# Step_Down.net
KiCad netlist of a schematic drawn in Altium Designer
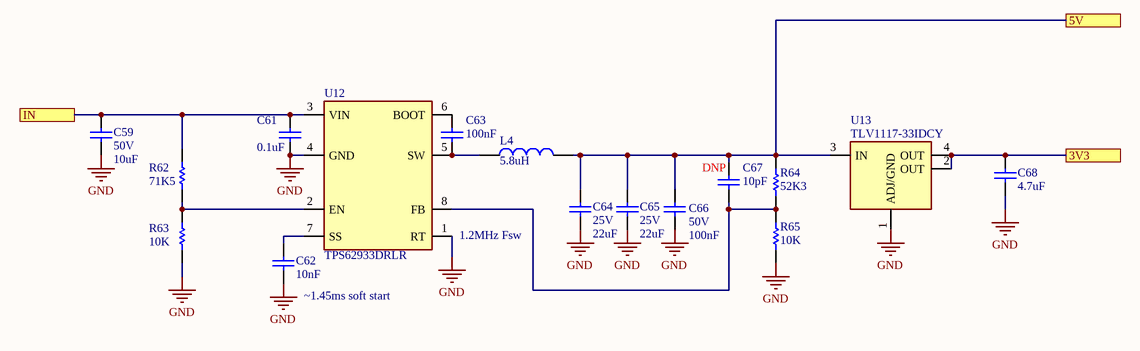
[diagram p0: Step_Down.SchDoc]

(export (version "E")
  (design (tool "Eeschema 10.0.6"))
  (components
    (comp (ref "C59")
      (value "CL32B106KBJNNNE")
      (footprint "CAPC1210X090")
      (description "10 µF ±10% 50V Ceramic Capacitor X7R 1210 (3225 Metric)")
      (fields
        (field (name "DISTRIBUTOR PART NUMBER") "1276-3387-1-ND")
        (field (name "TOLERANCE") "10%")
        (field (name "VOLTAGE RATING") "50V")
        (field (name "CAPACITANCE") "10uF")
      )
      (libsource (lib "Ahristi_Library") (part "CL32B106KBJNNNE"))
    )
    (comp (ref "C61")
      (value "CL05B104KB5NNNC")
      (footprint "CAPC0402X020")
      (description "0.1 µF ±10% 50V Ceramic Capacitor X7R 0402 (1005 Metric)")
      (fields
        (field (name "TOLERANCE") "10%")
        (field (name "DISTRIBUTOR PART NUMBER") "1276-CL05B104KB5NNNCCT-ND")
        (field (name "CAPACITANCE") "0.1uF")
      )
      (libsource (lib "Ahristi_Library") (part "CL05B104KB5NNNC"))
    )
    (comp (ref "C62")
      (value "CL10B103KB8NNNC")
      (footprint "CAPC0603X060")
      (description "10nF ±10% 50V Ceramic Capacitor X7R 0603 (1608 Metric)")
      (fields
        (field (name "DISTRIBUTOR PART NUMBER") "1276-1009-1-ND")
        (field (name "TOLERANCE") "10%")
        (field (name "CAPACITANCE") "10nF")
      )
      (libsource (lib "Ahristi_Library") (part "CL10B103KB8NNNC"))
    )
    (comp (ref "C63")
      (value "C0603C104K5RACTU")
      (footprint "CAPC0603X040")
      (description "0.1 µF ±10% 50V Ceramic Capacitor X7R 0603 (1608 Metric)")
      (fields
        (field (name "DISTRIBUTOR PART NUMBER") "399-C0603C104K5RACTUCT-ND")
        (field (name "TOLERANCE") "10%")
        (field (name "CAPACITANCE") "100nF")
      )
      (libsource (lib "Ahristi_Library") (part "C0603C104K5RACTU"))
    )
    (comp (ref "C64")
      (value "CL32B226KAJNNNE")
      (footprint "CAPC1210X090")
      (description "22 µF ±10% 25V Ceramic Capacitor X7R 1210 (3225 Metric)")
      (fields
        (field (name "DISTRIBUTOR PART NUMBER") "1276-3392-1-ND")
        (field (name "TOLERANCE") "10%")
        (field (name "VOLTAGE RATING") "25V")
        (field (name "CAPACITANCE") "22uF")
      )
      (libsource (lib "Ahristi_Library") (part "CL32B226KAJNNNE"))
    )
    (comp (ref "C65")
      (value "CL32B226KAJNNNE")
      (footprint "CAPC1210X090")
      (description "22 µF ±10% 25V Ceramic Capacitor X7R 1210 (3225 Metric)")
      (fields
        (field (name "DISTRIBUTOR PART NUMBER") "1276-3392-1-ND")
        (field (name "TOLERANCE") "10%")
        (field (name "VOLTAGE RATING") "25V")
        (field (name "CAPACITANCE") "22uF")
      )
      (libsource (lib "Ahristi_Library") (part "CL32B226KAJNNNE"))
    )
    (comp (ref "C66")
      (value "C0603C104K5RACTU")
      (footprint "CAPC0603X040")
      (description "0.1 µF ±10% 50V Ceramic Capacitor X7R 0603 (1608 Metric)")
      (fields
        (field (name "DISTRIBUTOR PART NUMBER") "399-C0603C104K5RACTUCT-ND")
        (field (name "TOLERANCE") "10%")
        (field (name "VOLTAGE RATING") "50V")
        (field (name "CAPACITANCE") "100nF")
      )
      (libsource (lib "Ahristi_Library") (part "C0603C104K5RACTU"))
    )
    (comp (ref "C67")
      (value "C0603C104K5RACTU")
      (footprint "CAPC0603X040")
      (description "10 pF ±5% 50V Ceramic Capacitor C0G, NP0 0603 (1608 Metric)")
      (fields
        (field (name "PART NUMBER") "C0603C100J5GACTU")
        (field (name "DISTRIBUTOR PART NUMBER") "399-C0603C100J5GACTUCT-ND")
        (field (name "CAPACITANCE") "10pF")
      )
      (libsource (lib "Ahristi_Library") (part "C0603C100J5GACTU"))
    )
    (comp (ref "C68")
      (value "CL21B475KOFNFNE")
      (footprint "CAPC0805X060")
      (description "4.7 µF ±10% 16V Ceramic Capacitor X7R 0805 (2012 Metric)")
      (fields
        (field (name "DISTRIBUTOR PART NUMBER") "1276-2970-1-ND")
        (field (name "TOLERANCE") "10%")
        (field (name "CAPACITANCE") "4.7uF")
      )
      (libsource (lib "Ahristi_Library") (part "CL21B475KOFNFNE"))
    )
    (comp (ref "L4")
      (value "744316560")
      (footprint "744316560")
      (description "Inductor 5.6uH 4.5A Shielded 28.5mOhm SMD")
      (fields (field (name "DISTRIBUTOR PART NUMBER") "732-6183-1-ND"))
      (libsource (lib "Ahristi_Library") (part "744316560"))
    )
    (comp (ref "R62")
      (value "RMCF0603FT71K5")
      (footprint "RESC0603")
      (description "71.5 kOhms ±1% 0.1W, 1/10W Chip Resistor 0603 (1608 Metric) Automotive AEC-Q200 Thick Film")
      (fields
        (field (name "TOLERANCE") "1%")
        (field (name "DISTRIBUTOR PART NUMBER") "RMCF0603FT71K5CT-ND")
        (field (name "RESISTANCE") "71K5")
      )
      (libsource (lib "Ahristi_Library") (part "RMCF0603FT71K5"))
    )
    (comp (ref "R63")
      (value "RMCF0603FT10K0")
      (footprint "RESC0603")
      (description "10 kOhms ±1% 0.1W, 1/10W Chip Resistor 0603 (1608 Metric) Automotive AEC-Q200 Thick Film")
      (fields
        (field (name "TOLERANCE") "1%")
        (field (name "DISTRIBUTOR PART NUMBER") "RMCF0603FT10K0CT-ND")
        (field (name "RESISTANCE") "10K")
      )
      (libsource (lib "Ahristi_Library") (part "RMCF0603FT10K0"))
    )
    (comp (ref "R64")
      (value "RMCF0603FT52K3")
      (footprint "RESC0603")
      (description "52.3 kOhms ±1% 0.1W, 1/10W Chip Resistor 0603 (1608 Metric) Automotive AEC-Q200 Thick Film")
      (fields
        (field (name "TOLERANCE") "1%")
        (field (name "DISTRIBUTOR PART NUMBER") "RMCF0603FT174KCT-ND")
        (field (name "RESISTANCE") "52K3")
      )
      (libsource (lib "Ahristi_Library") (part "RMCF0603FT52K3"))
    )
    (comp (ref "R65")
      (value "RMCF0603FT10K0")
      (footprint "RESC0603")
      (description "10 kOhms ±1% 0.1W, 1/10W Chip Resistor 0603 (1608 Metric) Automotive AEC-Q200 Thick Film")
      (fields
        (field (name "TOLERANCE") "1%")
        (field (name "DISTRIBUTOR PART NUMBER") "RMCF0603FT10K0CT-ND")
        (field (name "RESISTANCE") "10K")
      )
      (libsource (lib "Ahristi_Library") (part "RMCF0603FT10K0"))
    )
    (comp (ref "U12")
      (value "TPS62933DRLR")
      (footprint "SOT-583")
      (description "Buck Switching Regulator IC Positive Adjustable 0.8V 1 Output 3A SOT-583")
      (fields (field (name "DISTRIBUTOR PART NUMBER") "296-TPS62933DRLRCT-ND"))
      (libsource (lib "Ahristi_Library") (part "TPS62933DRLR"))
    )
    (comp (ref "U13")
      (value "TLV1117-33IDCY")
      (footprint "TLV1117-33IDCY")
      (description "3.3V 800-mA, 15-V, linear voltage regulator 4-SOT-223 -40 to 125")
      (fields (field (name "DISTRIBUTOR PART NUMBER") "296-26777-5-ND"))
      (libsource (lib "Ahristi_Library") (part "TLV1117-33IDCY"))
    )
  )
  (nets
    (net (code "1") (name "/3V3") (class "Default")
      (node (ref "C68") (pin "2") (pinfunction "2_2") (pintype "passive"))
      (node (ref "U13") (pin "2") (pinfunction "OUT_2") (pintype "passive"))
      (node (ref "U13") (pin "4") (pinfunction "OUT_4") (pintype "passive"))
    )
    (net (code "2") (name "/5V") (class "Default")
      (node (ref "C64") (pin "2") (pinfunction "2_2") (pintype "passive"))
      (node (ref "C65") (pin "2") (pinfunction "2_2") (pintype "passive"))
      (node (ref "C66") (pin "2") (pinfunction "2_2") (pintype "passive"))
      (node (ref "C67") (pin "2") (pinfunction "2_2") (pintype "passive"))
      (node (ref "L4") (pin "2") (pinfunction "2_2") (pintype "passive"))
      (node (ref "R64") (pin "2") (pinfunction "2_2") (pintype "passive"))
      (node (ref "U13") (pin "3") (pinfunction "IN_3") (pintype "passive"))
    )
    (net (code "3") (name "/IN") (class "Default")
      (node (ref "C59") (pin "2") (pinfunction "2_2") (pintype "passive"))
      (node (ref "C61") (pin "2") (pinfunction "2_2") (pintype "passive"))
      (node (ref "R62") (pin "2") (pinfunction "2_2") (pintype "passive"))
      (node (ref "U12") (pin "3") (pinfunction "VIN_3") (pintype "passive"))
    )
    (net (code "4") (name "GND") (class "Default")
      (node (ref "C59") (pin "1") (pinfunction "1_1") (pintype "passive"))
      (node (ref "C61") (pin "1") (pinfunction "1_1") (pintype "passive"))
      (node (ref "C62") (pin "1") (pinfunction "1_1") (pintype "passive"))
      (node (ref "C64") (pin "1") (pinfunction "1_1") (pintype "passive"))
      (node (ref "C65") (pin "1") (pinfunction "1_1") (pintype "passive"))
      (node (ref "C66") (pin "1") (pinfunction "1_1") (pintype "passive"))
      (node (ref "C68") (pin "1") (pinfunction "1_1") (pintype "passive"))
      (node (ref "R63") (pin "1") (pinfunction "1_1") (pintype "passive"))
      (node (ref "R65") (pin "1") (pinfunction "1_1") (pintype "passive"))
      (node (ref "U12") (pin "1") (pinfunction "RT_1") (pintype "passive"))
      (node (ref "U12") (pin "4") (pinfunction "GND_4") (pintype "passive"))
      (node (ref "U13") (pin "1") (pinfunction "ADJ/GND_1") (pintype "passive"))
    )
    (net (code "5") (name "Net-(U12-BOOT)") (class "Default")
      (node (ref "C63") (pin "2") (pinfunction "2_2") (pintype "passive"))
      (node (ref "U12") (pin "6") (pinfunction "BOOT_6") (pintype "passive"))
    )
    (net (code "6") (name "Net-(U12-EN)") (class "Default")
      (node (ref "R62") (pin "1") (pinfunction "1_1") (pintype "passive"))
      (node (ref "R63") (pin "2") (pinfunction "2_2") (pintype "passive"))
      (node (ref "U12") (pin "2") (pinfunction "EN_2") (pintype "passive"))
    )
    (net (code "7") (name "Net-(U12-FB)") (class "Default")
      (node (ref "C67") (pin "1") (pinfunction "1_1") (pintype "passive"))
      (node (ref "R64") (pin "1") (pinfunction "1_1") (pintype "passive"))
      (node (ref "R65") (pin "2") (pinfunction "2_2") (pintype "passive"))
      (node (ref "U12") (pin "8") (pinfunction "FB_8") (pintype "passive"))
    )
    (net (code "8") (name "Net-(U12-SS)") (class "Default")
      (node (ref "C62") (pin "2") (pinfunction "2_2") (pintype "passive"))
      (node (ref "U12") (pin "7") (pinfunction "SS_7") (pintype "passive"))
    )
    (net (code "9") (name "Net-(U12-SW)") (class "Default")
      (node (ref "C63") (pin "1") (pinfunction "1_1") (pintype "passive"))
      (node (ref "L4") (pin "1") (pinfunction "1_1") (pintype "passive"))
      (node (ref "U12") (pin "5") (pinfunction "SW_5") (pintype "passive"))
    )
  )
)
